# Display.net
KiCad netlist of a schematic drawn in Altium Designer
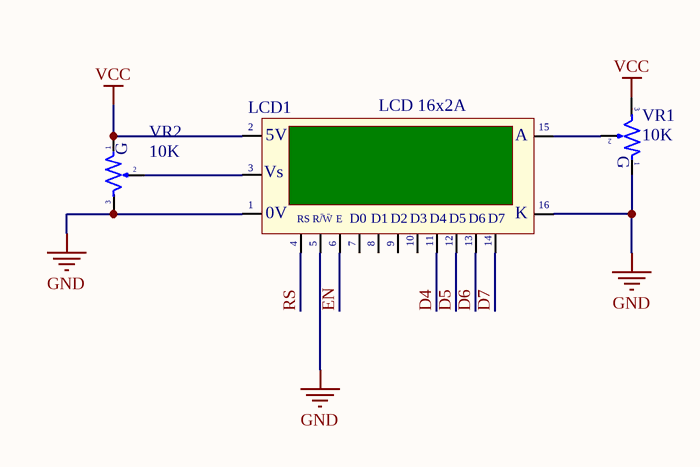
[diagram p0: Display.SchDoc]

(export (version "E")
  (design (tool "Eeschema 10.0.6"))
  (components
    (comp (ref "LCD1")
      (value "LCD 16x2A")
      (footprint "LCD16X2")
      (description "LCD dipslay 16 char, 2 line")
      (libsource (lib "LIBRARY") (part "LCD16x2A"))
    )
    (comp (ref "VR1")
      (value "10K")
      (footprint "VR-S2")
      (description "Var Resistor")
      (libsource (lib "LIBRARY") (part "VR-S"))
    )
    (comp (ref "VR2")
      (value "10K")
      (footprint "VR-S2")
      (description "Var Resistor")
      (libsource (lib "LIBRARY") (part "VR-S"))
    )
  )
  (nets
    (net (code "1") (name "/D4") (class "Default")
      (node (ref "LCD1") (pin "11") (pinfunction "D4_11") (pintype "passive"))
    )
    (net (code "2") (name "/D5") (class "Default")
      (node (ref "LCD1") (pin "12") (pinfunction "D5_12") (pintype "passive"))
    )
    (net (code "3") (name "/D6") (class "Default")
      (node (ref "LCD1") (pin "13") (pinfunction "D6_13") (pintype "passive"))
    )
    (net (code "4") (name "/D7") (class "Default")
      (node (ref "LCD1") (pin "14") (pinfunction "D7_14") (pintype "passive"))
    )
    (net (code "5") (name "/EN") (class "Default")
      (node (ref "LCD1") (pin "6") (pinfunction "~{EN}_6") (pintype "passive"))
    )
    (net (code "6") (name "/RS") (class "Default")
      (node (ref "LCD1") (pin "4") (pinfunction "RS_4") (pintype "passive"))
    )
    (net (code "7") (name "GND") (class "Default")
      (node (ref "LCD1") (pin "1") (pinfunction "GND_1") (pintype "passive"))
      (node (ref "LCD1") (pin "16") (pinfunction "K_16") (pintype "passive"))
      (node (ref "LCD1") (pin "5") (pinfunction "R/~{W}_5") (pintype "passive"))
      (node (ref "VR1") (pin "1") (pinfunction "1_1") (pintype "passive"))
      (node (ref "VR2") (pin "3") (pinfunction "3_3") (pintype "passive"))
    )
    (net (code "8") (name "Net-(LCD1-A)") (class "Default")
      (node (ref "LCD1") (pin "15") (pinfunction "A_15") (pintype "passive"))
      (node (ref "VR1") (pin "2") (pinfunction "2_2") (pintype "passive"))
    )
    (net (code "9") (name "Net-(LCD1-VEE)") (class "Default")
      (node (ref "LCD1") (pin "3") (pinfunction "VEE_3") (pintype "passive"))
      (node (ref "VR2") (pin "2") (pinfunction "2_2") (pintype "passive"))
    )
    (net (code "10") (name "VCC") (class "Default")
      (node (ref "LCD1") (pin "2") (pinfunction "VDD_2") (pintype "passive"))
      (node (ref "VR1") (pin "3") (pinfunction "3_3") (pintype "passive"))
      (node (ref "VR2") (pin "1") (pinfunction "1_1") (pintype "passive"))
    )
    (net (code "11") (name "unconnected-(LCD1-D0-Pad7)") (class "Default")
      (node (ref "LCD1") (pin "7") (pinfunction "D0_7") (pintype "passive"))
    )
    (net (code "12") (name "unconnected-(LCD1-D1-Pad8)") (class "Default")
      (node (ref "LCD1") (pin "8") (pinfunction "D1_8") (pintype "passive"))
    )
    (net (code "13") (name "unconnected-(LCD1-D2-Pad9)") (class "Default")
      (node (ref "LCD1") (pin "9") (pinfunction "D2_9") (pintype "passive"))
    )
    (net (code "14") (name "unconnected-(LCD1-D3-Pad10)") (class "Default")
      (node (ref "LCD1") (pin "10") (pinfunction "D3_10") (pintype "passive"))
    )
  )
)
